# Primary_MCU.net
KiCad netlist of a schematic drawn in Altium Designer
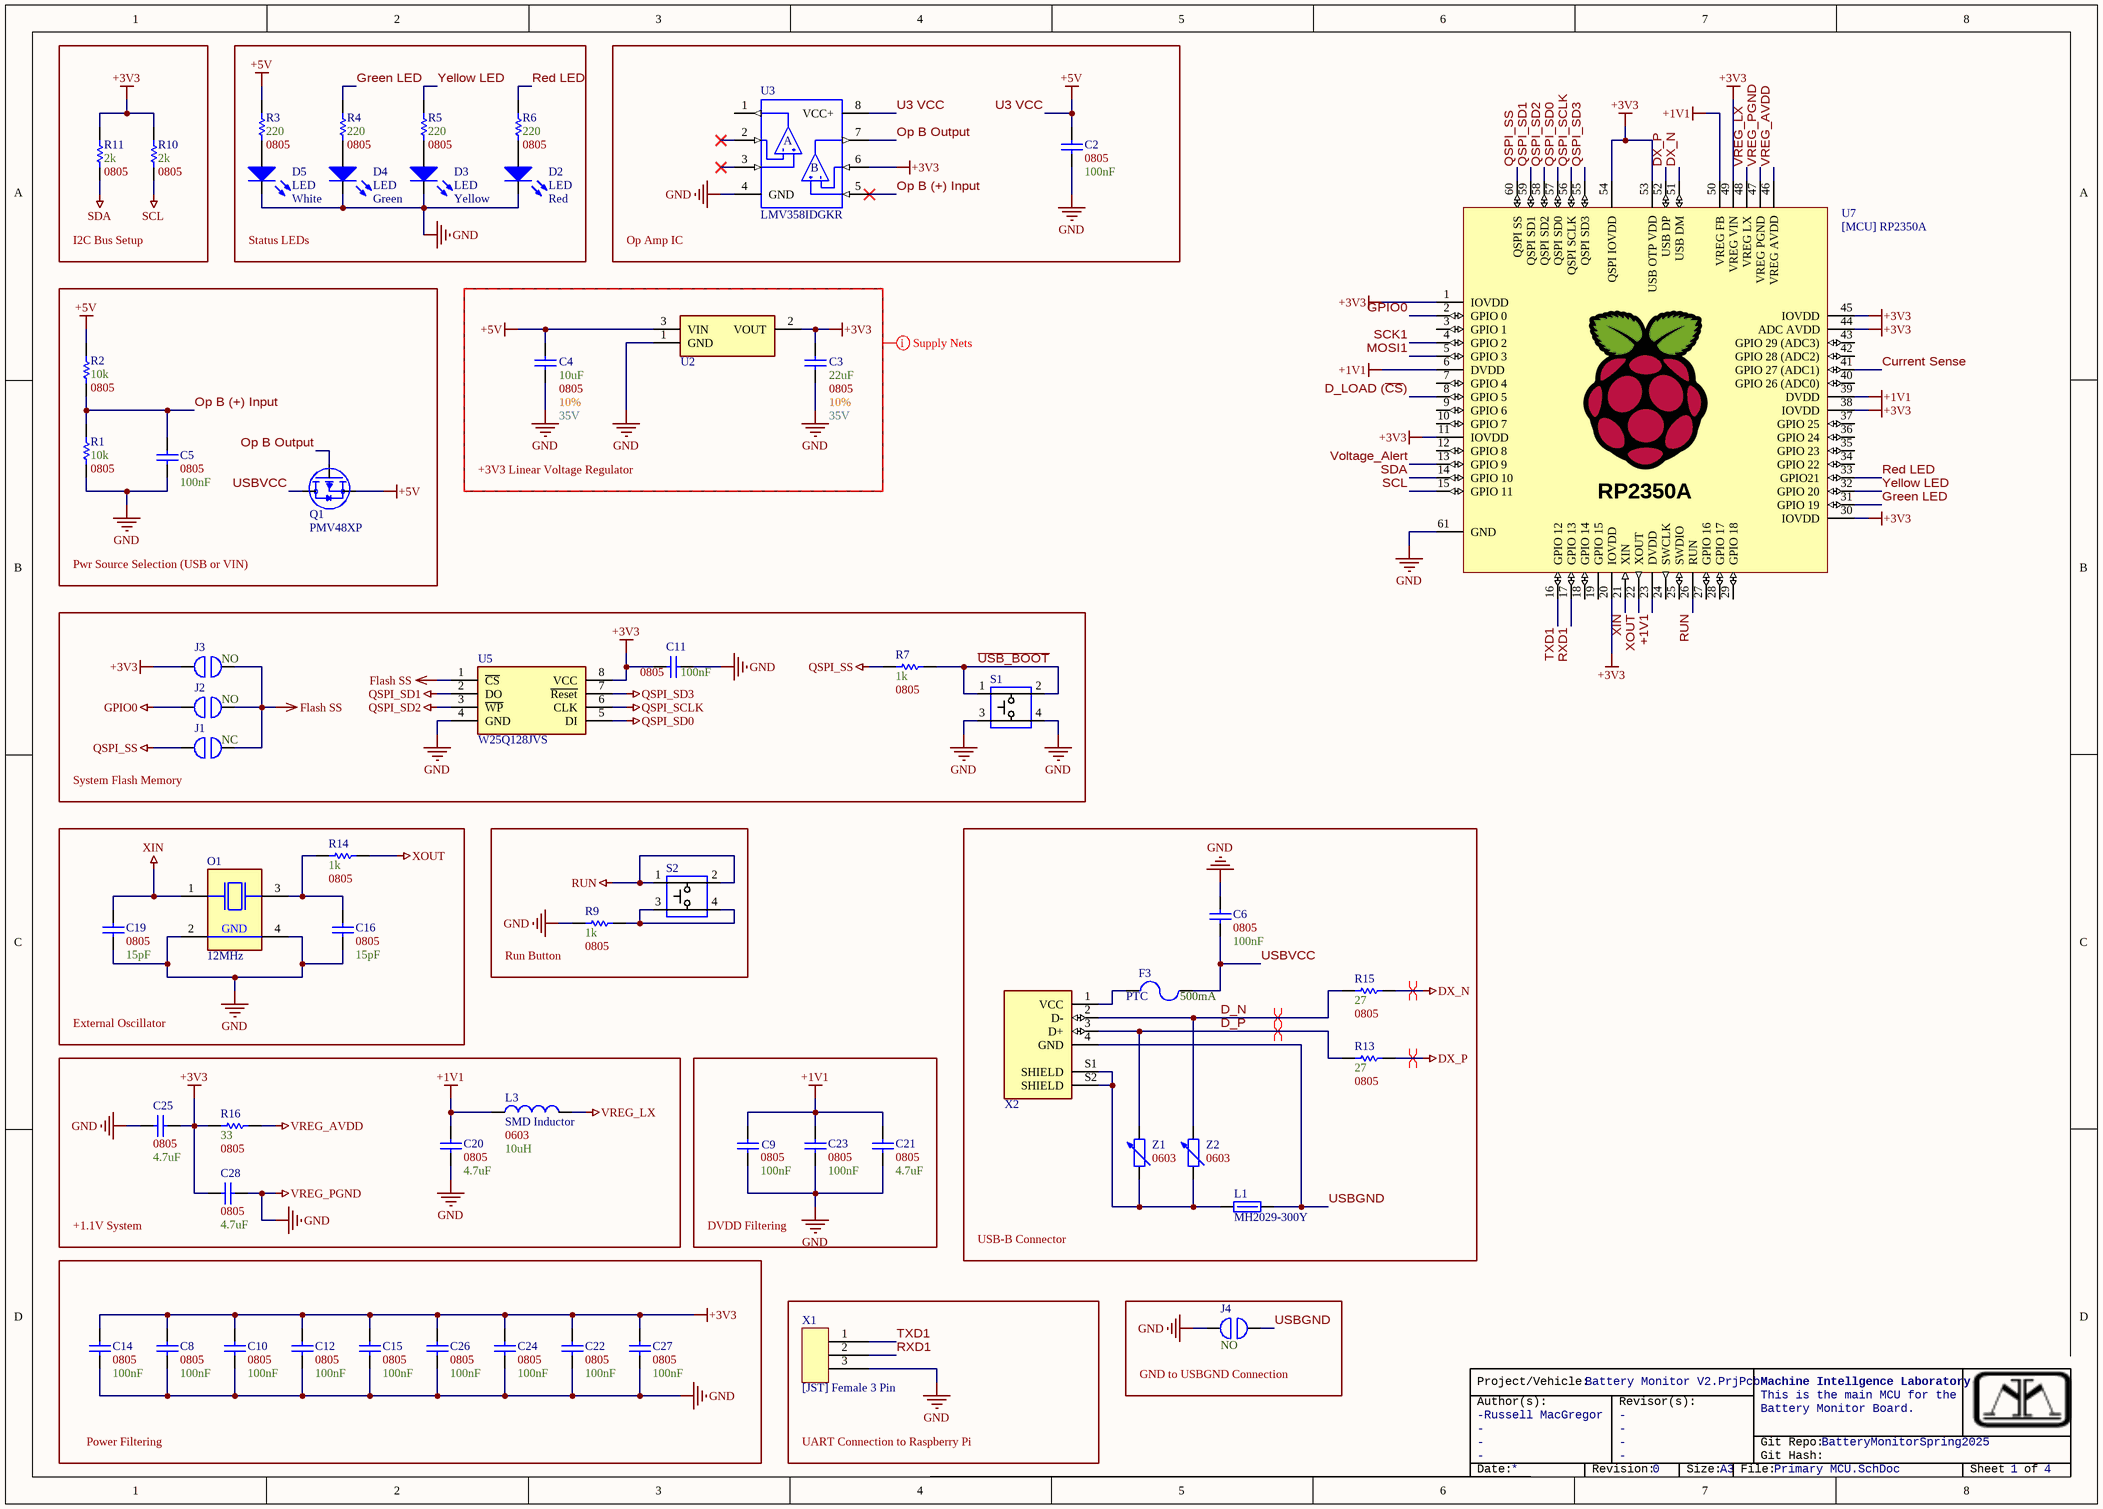
[diagram p0: Primary MCU.SchDoc]

(export (version "E")
  (design (tool "Eeschema 10.0.6"))
  (components
    (comp (ref "C2")
      (value "[Cap] SMD Nonpolarized")
      (footprint "[Cap] SMD 0805")
      (fields (field (name "SIZE PACKAGE") "0805") (field (name "CAPACITANCE") "100nF"))
      (libsource (lib "RADM Components") (part "[Cap] SMD Nonpolarized"))
    )
    (comp (ref "C3")
      (value "SMD Nonpolarized")
      (footprint "[Cap] SMD 0805")
      (fields
        (field (name "VOLTAGE") "35V")
        (field (name "TOLERANCE") "10%")
        (field (name "SIZE PACKAGE") "0805")
        (field (name "CAPACITANCE") "22uF")
      )
      (libsource (lib "RADM Components") (part "[Cap] SMD Nonpolarized"))
    )
    (comp (ref "C4")
      (value "SMD Nonpolarized")
      (footprint "[Cap] SMD 0805")
      (fields
        (field (name "VOLTAGE") "35V")
        (field (name "TOLERANCE") "10%")
        (field (name "SIZE PACKAGE") "0805")
        (field (name "CAPACITANCE") "10uF")
      )
      (libsource (lib "RADM Components") (part "[Cap] SMD Nonpolarized"))
    )
    (comp (ref "C5")
      (value "[Cap] SMD Nonpolarized")
      (footprint "[Cap] SMD 0805")
      (fields (field (name "SIZE PACKAGE") "0805") (field (name "CAPACITANCE") "100nF"))
      (libsource (lib "RADM Components") (part "[Cap] SMD Nonpolarized"))
    )
    (comp (ref "C6")
      (value "[Cap] SMD Nonpolarized")
      (footprint "[Cap] SMD 0805")
      (fields (field (name "SIZE PACKAGE") "0805") (field (name "CAPACITANCE") "100nF"))
      (libsource (lib "RADM Components") (part "[Cap] SMD Nonpolarized"))
    )
    (comp (ref "C8")
      (value "[Cap] SMD Nonpolarized")
      (footprint "[Cap] SMD 0805")
      (fields (field (name "SIZE PACKAGE") "0805") (field (name "CAPACITANCE") "100nF"))
      (libsource (lib "RADM Components") (part "[Cap] SMD Nonpolarized"))
    )
    (comp (ref "C9")
      (value "[Cap] SMD Nonpolarized")
      (footprint "[Cap] SMD 0805")
      (fields (field (name "SIZE PACKAGE") "0805") (field (name "CAPACITANCE") "100nF"))
      (libsource (lib "RADM Components") (part "[Cap] SMD Nonpolarized"))
    )
    (comp (ref "C10")
      (value "[Cap] SMD Nonpolarized")
      (footprint "[Cap] SMD 0805")
      (fields (field (name "SIZE PACKAGE") "0805") (field (name "CAPACITANCE") "100nF"))
      (libsource (lib "RADM Components") (part "[Cap] SMD Nonpolarized"))
    )
    (comp (ref "C11")
      (value "[Cap] SMD Nonpolarized")
      (footprint "[Cap] SMD 0805")
      (fields (field (name "SIZE PACKAGE") "0805") (field (name "CAPACITANCE") "100nF"))
      (libsource (lib "RADM Components") (part "[Cap] SMD Nonpolarized"))
    )
    (comp (ref "C12")
      (value "[Cap] SMD Nonpolarized")
      (footprint "[Cap] SMD 0805")
      (fields (field (name "SIZE PACKAGE") "0805") (field (name "CAPACITANCE") "100nF"))
      (libsource (lib "RADM Components") (part "[Cap] SMD Nonpolarized"))
    )
    (comp (ref "C14")
      (value "[Cap] SMD Nonpolarized")
      (footprint "[Cap] SMD 0805")
      (fields (field (name "SIZE PACKAGE") "0805") (field (name "CAPACITANCE") "100nF"))
      (libsource (lib "RADM Components") (part "[Cap] SMD Nonpolarized"))
    )
    (comp (ref "C15")
      (value "[Cap] SMD Nonpolarized")
      (footprint "[Cap] SMD 0805")
      (fields (field (name "SIZE PACKAGE") "0805") (field (name "CAPACITANCE") "100nF"))
      (libsource (lib "RADM Components") (part "[Cap] SMD Nonpolarized"))
    )
    (comp (ref "C16")
      (value "[Cap] SMD Nonpolarized")
      (footprint "[Cap] SMD 0805")
      (fields (field (name "SIZE PACKAGE") "0805") (field (name "CAPACITANCE") "15pF"))
      (libsource (lib "RADM Components") (part "[Cap] SMD Nonpolarized"))
    )
    (comp (ref "C19")
      (value "[Cap] SMD Nonpolarized")
      (footprint "[Cap] SMD 0805")
      (fields (field (name "SIZE PACKAGE") "0805") (field (name "CAPACITANCE") "15pF"))
      (libsource (lib "RADM Components") (part "[Cap] SMD Nonpolarized"))
    )
    (comp (ref "C20")
      (value "[Cap] SMD Nonpolarized")
      (footprint "[Cap] SMD 0805")
      (fields (field (name "SIZE PACKAGE") "0805") (field (name "CAPACITANCE") "4.7uF"))
      (libsource (lib "RADM Components") (part "[Cap] SMD Nonpolarized"))
    )
    (comp (ref "C21")
      (value "[Cap] SMD Nonpolarized")
      (footprint "[Cap] SMD 0805")
      (fields (field (name "SIZE PACKAGE") "0805") (field (name "CAPACITANCE") "4.7uF"))
      (libsource (lib "RADM Components") (part "[Cap] SMD Nonpolarized"))
    )
    (comp (ref "C22")
      (value "[Cap] SMD Nonpolarized")
      (footprint "[Cap] SMD 0805")
      (fields (field (name "SIZE PACKAGE") "0805") (field (name "CAPACITANCE") "100nF"))
      (libsource (lib "RADM Components") (part "[Cap] SMD Nonpolarized"))
    )
    (comp (ref "C23")
      (value "[Cap] SMD Nonpolarized")
      (footprint "[Cap] SMD 0805")
      (fields (field (name "SIZE PACKAGE") "0805") (field (name "CAPACITANCE") "100nF"))
      (libsource (lib "RADM Components") (part "[Cap] SMD Nonpolarized"))
    )
    (comp (ref "C24")
      (value "[Cap] SMD Nonpolarized")
      (footprint "[Cap] SMD 0805")
      (fields (field (name "SIZE PACKAGE") "0805") (field (name "CAPACITANCE") "100nF"))
      (libsource (lib "RADM Components") (part "[Cap] SMD Nonpolarized"))
    )
    (comp (ref "C25")
      (value "[Cap] SMD Nonpolarized")
      (footprint "[Cap] SMD 0805")
      (fields (field (name "SIZE PACKAGE") "0805") (field (name "CAPACITANCE") "4.7uF"))
      (libsource (lib "RADM Components") (part "[Cap] SMD Nonpolarized"))
    )
    (comp (ref "C26")
      (value "[Cap] SMD Nonpolarized")
      (footprint "[Cap] SMD 0805")
      (fields (field (name "SIZE PACKAGE") "0805") (field (name "CAPACITANCE") "100nF"))
      (libsource (lib "RADM Components") (part "[Cap] SMD Nonpolarized"))
    )
    (comp (ref "C27")
      (value "[Cap] SMD Nonpolarized")
      (footprint "[Cap] SMD 0805")
      (fields (field (name "SIZE PACKAGE") "0805") (field (name "CAPACITANCE") "100nF"))
      (libsource (lib "RADM Components") (part "[Cap] SMD Nonpolarized"))
    )
    (comp (ref "C28")
      (value "[Cap] SMD Nonpolarized")
      (footprint "[Cap] SMD 0805")
      (fields (field (name "SIZE PACKAGE") "0805") (field (name "CAPACITANCE") "4.7uF"))
      (libsource (lib "RADM Components") (part "[Cap] SMD Nonpolarized"))
    )
    (comp (ref "D2")
      (value "LED")
      (footprint "[LED] Thru-Hole, 3mm, Red")
      (description "3mm LED")
      (fields (field (name "COLOR") "Red"))
      (libsource (lib "RADM Components") (part "[LED] Thru-Hole 3mm"))
    )
    (comp (ref "D3")
      (value "LED")
      (footprint "[LED] Thru-Hole, 3mm, Yellow")
      (description "3mm LED")
      (fields (field (name "COLOR") "Yellow"))
      (libsource (lib "RADM Components") (part "[LED] Thru-Hole 3mm"))
    )
    (comp (ref "D4")
      (value "LED")
      (footprint "[LED] Thru-Hole, 3mm, Green")
      (description "3mm LED")
      (fields (field (name "COLOR") "Green"))
      (libsource (lib "RADM Components") (part "[LED] Thru-Hole 3mm"))
    )
    (comp (ref "D5")
      (value "LED")
      (footprint "[LED] Thru-Hole, 3mm, White")
      (description "3mm LED")
      (fields (field (name "COLOR") "White"))
      (libsource (lib "RADM Components") (part "[LED] Thru-Hole 3mm"))
    )
    (comp (ref "F3")
      (value "PTC")
      (footprint "[PTC] 500mA Trip")
      (description "MF-MSMF050-2\r\nJLC Part #: C17313")
      (fields (field (name "JLC PART #") "C17313") (field (name "TRIP CURRENT") "500mA"))
      (libsource (lib "RADM Components") (part "[PTC] 500mA Trip"))
    )
    (comp (ref "J1")
      (value "[Jump] SMD Jumper")
      (footprint "[Jumper] Solderable Jumper")
      (description "Solderable jumper")
      (fields (field (name "NO/NC") "NC"))
      (libsource (lib "RADM Components") (part "[Jump] SMD Jumper"))
    )
    (comp (ref "J2")
      (value "[Jump] SMD Jumper")
      (footprint "[Jumper] Solderable Jumper")
      (description "Solderable jumper")
      (fields (field (name "NO/NC") "NO"))
      (libsource (lib "RADM Components") (part "[Jump] SMD Jumper"))
    )
    (comp (ref "J3")
      (value "[Jump] SMD Jumper")
      (footprint "[Jumper] Solderable Jumper")
      (description "Solderable jumper")
      (fields (field (name "NO/NC") "NO"))
      (libsource (lib "RADM Components") (part "[Jump] SMD Jumper"))
    )
    (comp (ref "J4")
      (value "[Jump] SMD Jumper")
      (footprint "[Jumper] Solderable Jumper")
      (description "Solderable jumper")
      (fields (field (name "NO/NC") "NO"))
      (libsource (lib "RADM Components") (part "[Jump] SMD Jumper"))
    )
    (comp (ref "L1")
      (value "MH2029-300Y")
      (footprint "[Ferrite] SMD Bead 0805 (1)")
      (description "652-MH2029-300Y")
      (libsource (lib "RADM Components") (part "[Ferrite] SMD Ferrite Bead (1)"))
    )
    (comp (ref "L3")
      (value "SMD Inductor")
      (footprint "[Inductor] SMD 0603")
      (fields (field (name "SIZE PACKAGE") "0603") (field (name "INDUCTANCE") "10uH"))
      (libsource (lib "RADM Components") (part "[Inductor] SMD Inductor"))
    )
    (comp (ref "O1")
      (value "12MHz")
      (footprint "[XTAL] SMD 12MHz")
      (description "815-ABM8-272-T3")
      (libsource (lib "RADM Components") (part "[XTAL] SMD 12MHz"))
    )
    (comp (ref "Q1")
      (value "PMV48XP")
      (footprint "[FET] P-Channel Mosfet")
      (fields (field (name "JLC PART #") "C2959854"))
      (libsource (lib "RADM Components") (part "[FET] P-Channel MOSFET"))
    )
    (comp (ref "R1")
      (value "[Res] SMD Resistor")
      (footprint "[Res] SMD 0805")
      (fields (field (name "RESISTANCE") "10k") (field (name "SIZE PACKAGE") "0805"))
      (libsource (lib "RADM Components") (part "[Res] SMD Resistor"))
    )
    (comp (ref "R2")
      (value "[Res] SMD Resistor")
      (footprint "[Res] SMD 0805")
      (fields (field (name "RESISTANCE") "10k") (field (name "SIZE PACKAGE") "0805"))
      (libsource (lib "RADM Components") (part "[Res] SMD Resistor"))
    )
    (comp (ref "R3")
      (value "[Res] SMD Resistor")
      (footprint "[Res] SMD 0805")
      (fields (field (name "RESISTANCE") "220") (field (name "SIZE PACKAGE") "0805"))
      (libsource (lib "RADM Components") (part "[Res] SMD Resistor"))
    )
    (comp (ref "R4")
      (value "[Res] SMD Resistor")
      (footprint "[Res] SMD 0805")
      (fields (field (name "RESISTANCE") "220") (field (name "SIZE PACKAGE") "0805"))
      (libsource (lib "RADM Components") (part "[Res] SMD Resistor"))
    )
    (comp (ref "R5")
      (value "[Res] SMD Resistor")
      (footprint "[Res] SMD 0805")
      (fields (field (name "RESISTANCE") "220") (field (name "SIZE PACKAGE") "0805"))
      (libsource (lib "RADM Components") (part "[Res] SMD Resistor"))
    )
    (comp (ref "R6")
      (value "[Res] SMD Resistor")
      (footprint "[Res] SMD 0805")
      (fields (field (name "RESISTANCE") "220") (field (name "SIZE PACKAGE") "0805"))
      (libsource (lib "RADM Components") (part "[Res] SMD Resistor"))
    )
    (comp (ref "R7")
      (value "[Res] SMD Resistor")
      (footprint "[Res] SMD 0805")
      (fields (field (name "RESISTANCE") "1k") (field (name "SIZE PACKAGE") "0805"))
      (libsource (lib "RADM Components") (part "[Res] SMD Resistor"))
    )
    (comp (ref "R9")
      (value "[Res] SMD Resistor")
      (footprint "[Res] SMD 0805")
      (fields (field (name "RESISTANCE") "1k") (field (name "SIZE PACKAGE") "0805"))
      (libsource (lib "RADM Components") (part "[Res] SMD Resistor"))
    )
    (comp (ref "R10")
      (value "[Res] SMD Resistor")
      (footprint "[Res] SMD 0805")
      (fields (field (name "RESISTANCE") "2k") (field (name "SIZE PACKAGE") "0805"))
      (libsource (lib "RADM Components") (part "[Res] SMD Resistor"))
    )
    (comp (ref "R11")
      (value "[Res] SMD Resistor")
      (footprint "[Res] SMD 0805")
      (fields (field (name "RESISTANCE") "2k") (field (name "SIZE PACKAGE") "0805"))
      (libsource (lib "RADM Components") (part "[Res] SMD Resistor"))
    )
    (comp (ref "R13")
      (value "[Res] SMD Resistor")
      (footprint "[Res] SMD 0805")
      (fields (field (name "RESISTANCE") "27") (field (name "SIZE PACKAGE") "0805"))
      (libsource (lib "RADM Components") (part "[Res] SMD Resistor"))
    )
    (comp (ref "R14")
      (value "[Res] SMD Resistor")
      (footprint "[Res] SMD 0805")
      (fields (field (name "RESISTANCE") "1k") (field (name "SIZE PACKAGE") "0805"))
      (libsource (lib "RADM Components") (part "[Res] SMD Resistor"))
    )
    (comp (ref "R15")
      (value "[Res] SMD Resistor")
      (footprint "[Res] SMD 0805")
      (fields (field (name "RESISTANCE") "27") (field (name "SIZE PACKAGE") "0805"))
      (libsource (lib "RADM Components") (part "[Res] SMD Resistor"))
    )
    (comp (ref "R16")
      (value "[Res] SMD Resistor")
      (footprint "[Res] SMD 0805")
      (fields (field (name "RESISTANCE") "33") (field (name "SIZE PACKAGE") "0805"))
      (libsource (lib "RADM Components") (part "[Res] SMD Resistor"))
    )
    (comp (ref "S1")
      (value "Standard pushbutton")
      (footprint "[Switch] Pushbutton")
      (libsource (lib "RADM Components") (part "[Switch] Pushbutton"))
    )
    (comp (ref "S2")
      (value "Standard pushbutton")
      (footprint "[Switch] Pushbutton")
      (libsource (lib "RADM Components") (part "[Switch] Pushbutton"))
    )
    (comp (ref "U2")
      (value "3V3 1A")
      (footprint "[Reg] 3V3 Regulator (2)")
      (description "AZ1117CH-3.3TRG1")
      (libsource (lib "RADM Components") (part "[Reg] 3V3 Regulator (2)"))
    )
    (comp (ref "U3")
      (value "LMV358IDGKR")
      (footprint "[IC] Dual Op-Ap")
      (fields (field (name "JLC PART #") "C105242"))
      (libsource (lib "RADM Components") (part "[IC] Dual Op-Amp"))
    )
    (comp (ref "U5")
      (value "W25Q128JVS")
      (footprint "[IC] 16Mb Flash Memory")
      (description "W25Q128JVSIQ TR")
      (libsource (lib "RADM Components") (part "[IC] 16Mb Flash Memory"))
    )
    (comp (ref "U7")
      (value "[MCU] RP2350A")
      (footprint "[MCU] RP2350A")
      (libsource (lib "RADM Components") (part "[MCU] RP2350A"))
    )
    (comp (ref "X1")
      (value "[JST] Female 3 Pin")
      (footprint "[JST] 3PIN")
      (libsource (lib "RADM Components") (part "[JST] Female 3 Pin"))
    )
    (comp (ref "X2")
      (value "[Port] USB Type-B Female (Thru-Hole)")
      (footprint "[Port] USB Type-B Thru-Hole")
      (description "USB-B-S-F-B-TH")
      (fields (field (name "JLC PART #") "C5714571"))
      (libsource (lib "RADM Components") (part "[Port] USB Type-B Female (Thru-Hole)"))
    )
    (comp (ref "Z1")
      (value "[Inductor] SMD Varistor")
      (footprint "[Inductor] SMD Varistor 0603")
      (fields (field (name "JLC PART #") "C840634") (field (name "SIZE PACKAGE") "0603"))
      (libsource (lib "RADM Components") (part "[Inductor] SMD Varistor"))
    )
    (comp (ref "Z2")
      (value "[Inductor] SMD Varistor")
      (footprint "[Inductor] SMD Varistor 0603")
      (fields (field (name "JLC PART #") "C840634") (field (name "SIZE PACKAGE") "0603"))
      (libsource (lib "RADM Components") (part "[Inductor] SMD Varistor"))
    )
  )
  (nets
    (net (code "1") (name "+1V1") (class "Default")
      (node (ref "C20") (pin "2") (pinfunction "2_2") (pintype "passive"))
      (node (ref "C21") (pin "2") (pinfunction "2_2") (pintype "passive"))
      (node (ref "C23") (pin "2") (pinfunction "2_2") (pintype "passive"))
      (node (ref "C9") (pin "2") (pinfunction "2_2") (pintype "passive"))
      (node (ref "L3") (pin "1") (pinfunction "1_1") (pintype "passive"))
      (node (ref "U7") (pin "23") (pinfunction "DVDD_23") (pintype "power_in"))
      (node (ref "U7") (pin "39") (pinfunction "DVDD_39") (pintype "power_in"))
      (node (ref "U7") (pin "50") (pinfunction "VREG_FB_50") (pintype "power_in"))
      (node (ref "U7") (pin "6") (pinfunction "DVDD_6") (pintype "power_in"))
    )
    (net (code "2") (name "+3V3") (class "Default")
      (node (ref "C10") (pin "2") (pinfunction "2_2") (pintype "passive"))
      (node (ref "C11") (pin "2") (pinfunction "2_2") (pintype "passive"))
      (node (ref "C12") (pin "2") (pinfunction "2_2") (pintype "passive"))
      (node (ref "C14") (pin "2") (pinfunction "2_2") (pintype "passive"))
      (node (ref "C15") (pin "2") (pinfunction "2_2") (pintype "passive"))
      (node (ref "C22") (pin "2") (pinfunction "2_2") (pintype "passive"))
      (node (ref "C24") (pin "2") (pinfunction "2_2") (pintype "passive"))
      (node (ref "C25") (pin "1") (pinfunction "1_1") (pintype "passive"))
      (node (ref "C26") (pin "2") (pinfunction "2_2") (pintype "passive"))
      (node (ref "C27") (pin "2") (pinfunction "2_2") (pintype "passive"))
      (node (ref "C28") (pin "2") (pinfunction "2_2") (pintype "passive"))
      (node (ref "C3") (pin "2") (pinfunction "2_2") (pintype "passive"))
      (node (ref "C8") (pin "2") (pinfunction "2_2") (pintype "passive"))
      (node (ref "J3") (pin "1") (pintype "passive"))
      (node (ref "R10") (pin "2") (pinfunction "2_2") (pintype "passive"))
      (node (ref "R11") (pin "2") (pinfunction "2_2") (pintype "passive"))
      (node (ref "R16") (pin "2") (pinfunction "2_2") (pintype "passive"))
      (node (ref "U2") (pin "2") (pinfunction "VOUT_2") (pintype "passive"))
      (node (ref "U3") (pin "6") (pinfunction "2IN-_6") (pintype "input"))
      (node (ref "U5") (pin "8") (pinfunction "VCC_8") (pintype "passive"))
      (node (ref "U7") (pin "1") (pinfunction "IOVDD_1") (pintype "power_in"))
      (node (ref "U7") (pin "11") (pinfunction "IOVDD_11") (pintype "power_in"))
      (node (ref "U7") (pin "20") (pinfunction "IOVDD_20") (pintype "power_in"))
      (node (ref "U7") (pin "30") (pinfunction "IOVDD_30") (pintype "power_in"))
      (node (ref "U7") (pin "38") (pinfunction "IOVDD_38") (pintype "power_in"))
      (node (ref "U7") (pin "44") (pinfunction "ADC_AVDD_44") (pintype "power_in"))
      (node (ref "U7") (pin "45") (pinfunction "IOVDD_45") (pintype "power_in"))
      (node (ref "U7") (pin "49") (pinfunction "VREG_VIN_49") (pintype "power_in"))
      (node (ref "U7") (pin "53") (pinfunction "USB_OTP_VDD_53") (pintype "power_in"))
      (node (ref "U7") (pin "54") (pinfunction "QSPI_IOVDD_54") (pintype "power_in"))
    )
    (net (code "3") (name "+5V") (class "Default")
      (node (ref "C2") (pin "2") (pinfunction "2_2") (pintype "passive"))
      (node (ref "C4") (pin "2") (pinfunction "2_2") (pintype "passive"))
      (node (ref "Q1") (pin "2") (pinfunction "S_2") (pintype "passive"))
      (node (ref "R2") (pin "2") (pinfunction "2_2") (pintype "passive"))
      (node (ref "R3") (pin "1") (pinfunction "1_1") (pintype "passive"))
      (node (ref "U2") (pin "3") (pinfunction "VIN_3") (pintype "passive"))
      (node (ref "U3") (pin "8") (pinfunction "VCC+_8") (pintype "power_in"))
    )
    (net (code "4") (name "/Current Sense") (class "Default")
      (node (ref "U7") (pin "41") (pinfunction "GPIO_27_(ADC1)_41") (pintype "bidirectional"))
    )
    (net (code "5") (name "/D_LOAD (~{CS})") (class "Default")
      (node (ref "U7") (pin "8") (pinfunction "GPIO_5_8") (pintype "bidirectional"))
    )
    (net (code "6") (name "/D_N") (class "Default")
      (node (ref "R15") (pin "2") (pinfunction "2_2") (pintype "passive"))
      (node (ref "X2") (pin "2") (pinfunction "D-_2") (pintype "bidirectional"))
      (node (ref "Z2") (pin "2") (pinfunction "2_2") (pintype "passive"))
    )
    (net (code "7") (name "/D_P") (class "Default")
      (node (ref "R13") (pin "2") (pinfunction "2_2") (pintype "passive"))
      (node (ref "X2") (pin "3") (pinfunction "D+_3") (pintype "bidirectional"))
      (node (ref "Z1") (pin "2") (pinfunction "2_2") (pintype "passive"))
    )
    (net (code "8") (name "/Green LED") (class "Default")
      (node (ref "R4") (pin "1") (pinfunction "1_1") (pintype "passive"))
      (node (ref "U7") (pin "31") (pinfunction "GPIO_19_31") (pintype "bidirectional"))
    )
    (net (code "9") (name "/MOSI1") (class "Default")
      (node (ref "U7") (pin "5") (pinfunction "GPIO_3_5") (pintype "bidirectional"))
    )
    (net (code "10") (name "/Op B (+) Input") (class "Default")
      (node (ref "C5") (pin "2") (pinfunction "2_2") (pintype "passive"))
      (node (ref "R1") (pin "2") (pinfunction "2_2") (pintype "passive"))
      (node (ref "R2") (pin "1") (pinfunction "1_1") (pintype "passive"))
      (node (ref "U3") (pin "5") (pinfunction "2IN+_5") (pintype "input"))
    )
    (net (code "11") (name "/Op B Output") (class "Default")
      (node (ref "Q1") (pin "1") (pinfunction "G_1") (pintype "passive"))
      (node (ref "U3") (pin "7") (pinfunction "2OUT_7") (pintype "output"))
    )
    (net (code "12") (name "/RXD1") (class "Default")
      (node (ref "U7") (pin "17") (pinfunction "GPIO_13_17") (pintype "bidirectional"))
      (node (ref "X1") (pin "2") (pintype "passive"))
    )
    (net (code "13") (name "/Red LED") (class "Default")
      (node (ref "R6") (pin "1") (pinfunction "1_1") (pintype "passive"))
      (node (ref "U7") (pin "33") (pinfunction "GPIO21_33") (pintype "bidirectional"))
    )
    (net (code "14") (name "/SCK1") (class "Default")
      (node (ref "U7") (pin "4") (pinfunction "GPIO_2_4") (pintype "bidirectional"))
    )
    (net (code "15") (name "/TXD1") (class "Default")
      (node (ref "U7") (pin "16") (pinfunction "GPIO_12_16") (pintype "bidirectional"))
      (node (ref "X1") (pin "1") (pintype "passive"))
    )
    (net (code "16") (name "/USBGND") (class "Default")
      (node (ref "J4") (pin "2") (pintype "passive"))
      (node (ref "L1") (pin "2") (pinfunction "2_2") (pintype "passive"))
      (node (ref "X2") (pin "4") (pinfunction "GND_4") (pintype "power_in"))
    )
    (net (code "17") (name "/USBVCC") (class "Default")
      (node (ref "C6") (pin "1") (pinfunction "1_1") (pintype "passive"))
      (node (ref "F3") (pin "2") (pinfunction "2_2") (pintype "passive"))
      (node (ref "Q1") (pin "3") (pinfunction "D_3") (pintype "passive"))
    )
    (net (code "18") (name "/Voltage_Alert") (class "Default")
      (node (ref "U7") (pin "13") (pinfunction "GPIO_9_13") (pintype "bidirectional"))
    )
    (net (code "19") (name "/Yellow LED") (class "Default")
      (node (ref "R5") (pin "1") (pinfunction "1_1") (pintype "passive"))
      (node (ref "U7") (pin "32") (pinfunction "GPIO_20_32") (pintype "bidirectional"))
    )
    (net (code "20") (name "/~{USB_BOOT}") (class "Default")
      (node (ref "R7") (pin "1") (pinfunction "1_1") (pintype "passive"))
      (node (ref "S1") (pin "1") (pintype "power_in"))
      (node (ref "S1") (pin "2") (pintype "power_in"))
    )
    (net (code "21") (name "DX_N") (class "Default")
      (node (ref "R15") (pin "1") (pinfunction "1_1") (pintype "passive"))
      (node (ref "U7") (pin "51") (pinfunction "USB_DM_51") (pintype "bidirectional"))
    )
    (net (code "22") (name "DX_P") (class "Default")
      (node (ref "R13") (pin "1") (pinfunction "1_1") (pintype "passive"))
      (node (ref "U7") (pin "52") (pinfunction "USB_DP_52") (pintype "bidirectional"))
    )
    (net (code "23") (name "Flash SS") (class "Default")
      (node (ref "J1") (pin "2") (pintype "passive"))
      (node (ref "J2") (pin "2") (pintype "passive"))
      (node (ref "J3") (pin "2") (pintype "passive"))
      (node (ref "U5") (pin "1") (pinfunction "~{CS}_1") (pintype "passive"))
    )
    (net (code "24") (name "GND") (class "Default")
      (node (ref "C10") (pin "1") (pinfunction "1_1") (pintype "passive"))
      (node (ref "C11") (pin "1") (pinfunction "1_1") (pintype "passive"))
      (node (ref "C12") (pin "1") (pinfunction "1_1") (pintype "passive"))
      (node (ref "C14") (pin "1") (pinfunction "1_1") (pintype "passive"))
      (node (ref "C15") (pin "1") (pinfunction "1_1") (pintype "passive"))
      (node (ref "C16") (pin "1") (pinfunction "1_1") (pintype "passive"))
      (node (ref "C19") (pin "1") (pinfunction "1_1") (pintype "passive"))
      (node (ref "C2") (pin "1") (pinfunction "1_1") (pintype "passive"))
      (node (ref "C20") (pin "1") (pinfunction "1_1") (pintype "passive"))
      (node (ref "C21") (pin "1") (pinfunction "1_1") (pintype "passive"))
      (node (ref "C22") (pin "1") (pinfunction "1_1") (pintype "passive"))
      (node (ref "C23") (pin "1") (pinfunction "1_1") (pintype "passive"))
      (node (ref "C24") (pin "1") (pinfunction "1_1") (pintype "passive"))
      (node (ref "C25") (pin "2") (pinfunction "2_2") (pintype "passive"))
      (node (ref "C26") (pin "1") (pinfunction "1_1") (pintype "passive"))
      (node (ref "C27") (pin "1") (pinfunction "1_1") (pintype "passive"))
      (node (ref "C28") (pin "1") (pinfunction "1_1") (pintype "passive"))
      (node (ref "C3") (pin "1") (pinfunction "1_1") (pintype "passive"))
      (node (ref "C4") (pin "1") (pinfunction "1_1") (pintype "passive"))
      (node (ref "C5") (pin "1") (pinfunction "1_1") (pintype "passive"))
      (node (ref "C6") (pin "2") (pinfunction "2_2") (pintype "passive"))
      (node (ref "C8") (pin "1") (pinfunction "1_1") (pintype "passive"))
      (node (ref "C9") (pin "1") (pinfunction "1_1") (pintype "passive"))
      (node (ref "D2") (pin "2") (pinfunction "K_2") (pintype "passive"))
      (node (ref "D3") (pin "2") (pinfunction "K_2") (pintype "passive"))
      (node (ref "D4") (pin "2") (pinfunction "K_2") (pintype "passive"))
      (node (ref "D5") (pin "2") (pinfunction "K_2") (pintype "passive"))
      (node (ref "J4") (pin "1") (pintype "passive"))
      (node (ref "O1") (pin "2") (pinfunction "GND_2") (pintype "power_in"))
      (node (ref "O1") (pin "4") (pinfunction "GND_4") (pintype "power_in"))
      (node (ref "R1") (pin "1") (pinfunction "1_1") (pintype "passive"))
      (node (ref "R9") (pin "2") (pinfunction "2_2") (pintype "passive"))
      (node (ref "S1") (pin "3") (pintype "power_in"))
      (node (ref "S1") (pin "4") (pintype "power_in"))
      (node (ref "U2") (pin "1") (pinfunction "GND_1") (pintype "passive"))
      (node (ref "U3") (pin "4") (pinfunction "GND_4") (pintype "power_in"))
      (node (ref "U5") (pin "4") (pinfunction "GND_4") (pintype "passive"))
      (node (ref "U7") (pin "47") (pinfunction "VREG_PGND_47") (pintype "power_in"))
      (node (ref "U7") (pin "61") (pinfunction "GND_61") (pintype "power_in"))
      (node (ref "X1") (pin "3") (pintype "passive"))
    )
    (net (code "25") (name "GPIO0") (class "Default")
      (node (ref "J2") (pin "1") (pintype "passive"))
      (node (ref "U7") (pin "2") (pinfunction "GPIO_0_2") (pintype "bidirectional"))
    )
    (net (code "26") (name "Net-(D2-A)") (class "Default")
      (node (ref "D2") (pin "1") (pinfunction "A_1") (pintype "passive"))
      (node (ref "R6") (pin "2") (pinfunction "2_2") (pintype "passive"))
    )
    (net (code "27") (name "Net-(D3-A)") (class "Default")
      (node (ref "D3") (pin "1") (pinfunction "A_1") (pintype "passive"))
      (node (ref "R5") (pin "2") (pinfunction "2_2") (pintype "passive"))
    )
    (net (code "28") (name "Net-(D4-A)") (class "Default")
      (node (ref "D4") (pin "1") (pinfunction "A_1") (pintype "passive"))
      (node (ref "R4") (pin "2") (pinfunction "2_2") (pintype "passive"))
    )
    (net (code "29") (name "Net-(D5-A)") (class "Default")
      (node (ref "D5") (pin "1") (pinfunction "A_1") (pintype "passive"))
      (node (ref "R3") (pin "2") (pinfunction "2_2") (pintype "passive"))
    )
    (net (code "30") (name "Net-(L1-Pad1)") (class "Default")
      (node (ref "L1") (pin "1") (pinfunction "1_1") (pintype "passive"))
      (node (ref "X2") (pin "S1") (pinfunction "SHIELD_S1") (pintype "passive"))
      (node (ref "X2") (pin "S2") (pinfunction "SHIELD_S2") (pintype "passive"))
      (node (ref "Z1") (pin "1") (pinfunction "1_1") (pintype "passive"))
      (node (ref "Z2") (pin "1") (pinfunction "1_1") (pintype "passive"))
    )
    (net (code "31") (name "Net-(O1-XTAL2)") (class "Default")
      (node (ref "C16") (pin "2") (pinfunction "2_2") (pintype "passive"))
      (node (ref "O1") (pin "3") (pinfunction "XTAL2_3") (pintype "power_in"))
      (node (ref "R14") (pin "2") (pinfunction "2_2") (pintype "passive"))
    )
    (net (code "32") (name "Net-(R9-Pad1)") (class "Default")
      (node (ref "R9") (pin "1") (pinfunction "1_1") (pintype "passive"))
      (node (ref "S2") (pin "3") (pintype "power_in"))
      (node (ref "S2") (pin "4") (pintype "power_in"))
    )
    (net (code "33") (name "Net-(X2-VCC)") (class "Default")
      (node (ref "F3") (pin "1") (pinfunction "1_1") (pintype "passive"))
      (node (ref "X2") (pin "1") (pinfunction "VCC_1") (pintype "power_in"))
    )
    (net (code "34") (name "QSPI_SCLK") (class "Default")
      (node (ref "U5") (pin "6") (pinfunction "CLK_6") (pintype "passive"))
      (node (ref "U7") (pin "56") (pinfunction "QSPI_SCLK_56") (pintype "bidirectional"))
    )
    (net (code "35") (name "QSPI_SD0") (class "Default")
      (node (ref "U5") (pin "5") (pinfunction "DI_5") (pintype "passive"))
      (node (ref "U7") (pin "57") (pinfunction "QSPI_SD0_57") (pintype "bidirectional"))
    )
    (net (code "36") (name "QSPI_SD1") (class "Default")
      (node (ref "U5") (pin "2") (pinfunction "DO_2") (pintype "passive"))
      (node (ref "U7") (pin "59") (pinfunction "QSPI_SD1_59") (pintype "bidirectional"))
    )
    (net (code "37") (name "QSPI_SD2") (class "Default")
      (node (ref "U5") (pin "3") (pinfunction "~{WP}_3") (pintype "passive"))
      (node (ref "U7") (pin "58") (pinfunction "QSPI_SD2_58") (pintype "bidirectional"))
    )
    (net (code "38") (name "QSPI_SD3") (class "Default")
      (node (ref "U5") (pin "7") (pinfunction "~{Reset}_7") (pintype "passive"))
      (node (ref "U7") (pin "55") (pinfunction "QSPI_SD3_55") (pintype "bidirectional"))
    )
    (net (code "39") (name "QSPI_SS") (class "Default")
      (node (ref "J1") (pin "1") (pintype "passive"))
      (node (ref "R7") (pin "2") (pinfunction "2_2") (pintype "passive"))
      (node (ref "U7") (pin "60") (pinfunction "QSPI_SS_60") (pintype "bidirectional"))
    )
    (net (code "40") (name "RUN") (class "Default")
      (node (ref "S2") (pin "1") (pintype "power_in"))
      (node (ref "S2") (pin "2") (pintype "power_in"))
      (node (ref "U7") (pin "26") (pinfunction "RUN_26") (pintype "passive"))
    )
    (net (code "41") (name "SCL") (class "Default")
      (node (ref "R10") (pin "1") (pinfunction "1_1") (pintype "passive"))
      (node (ref "U7") (pin "15") (pinfunction "GPIO_11_15") (pintype "bidirectional"))
    )
    (net (code "42") (name "SDA") (class "Default")
      (node (ref "R11") (pin "1") (pinfunction "1_1") (pintype "passive"))
      (node (ref "U7") (pin "14") (pinfunction "GPIO_10_14") (pintype "bidirectional"))
    )
    (net (code "43") (name "VREG_AVDD") (class "Default")
      (node (ref "R16") (pin "1") (pinfunction "1_1") (pintype "passive"))
      (node (ref "U7") (pin "46") (pinfunction "VREG_AVDD_46") (pintype "power_in"))
    )
    (net (code "44") (name "VREG_LX") (class "Default")
      (node (ref "L3") (pin "2") (pinfunction "2_2") (pintype "passive"))
      (node (ref "U7") (pin "48") (pinfunction "VREG_LX_48") (pintype "power_in"))
    )
    (net (code "45") (name "XIN") (class "Default")
      (node (ref "C19") (pin "2") (pinfunction "2_2") (pintype "passive"))
      (node (ref "O1") (pin "1") (pinfunction "XTAL1_1") (pintype "power_in"))
      (node (ref "U7") (pin "21") (pinfunction "XIN_21") (pintype "input"))
    )
    (net (code "46") (name "XOUT") (class "Default")
      (node (ref "R14") (pin "1") (pinfunction "1_1") (pintype "passive"))
      (node (ref "U7") (pin "22") (pinfunction "XOUT_22") (pintype "output"))
    )
    (net (code "47") (name "unconnected-(U3-1IN+-Pad3)") (class "Default")
      (node (ref "U3") (pin "3") (pinfunction "1IN+_3") (pintype "input+no_connect"))
    )
    (net (code "48") (name "unconnected-(U3-1IN--Pad2)") (class "Default")
      (node (ref "U3") (pin "2") (pinfunction "1IN-_2") (pintype "input+no_connect"))
    )
    (net (code "49") (name "unconnected-(U3-1OUT-Pad1)") (class "Default")
      (node (ref "U3") (pin "1") (pinfunction "1OUT_1") (pintype "output"))
    )
    (net (code "50") (name "unconnected-(U7-GPIO_1-Pad3)") (class "Default")
      (node (ref "U7") (pin "3") (pinfunction "GPIO_1_3") (pintype "bidirectional"))
    )
    (net (code "51") (name "unconnected-(U7-GPIO_4-Pad7)") (class "Default")
      (node (ref "U7") (pin "7") (pinfunction "GPIO_4_7") (pintype "bidirectional"))
    )
    (net (code "52") (name "unconnected-(U7-GPIO_6-Pad9)") (class "Default")
      (node (ref "U7") (pin "9") (pinfunction "GPIO_6_9") (pintype "bidirectional"))
    )
    (net (code "53") (name "unconnected-(U7-GPIO_7-Pad10)") (class "Default")
      (node (ref "U7") (pin "10") (pinfunction "GPIO_7_10") (pintype "bidirectional"))
    )
    (net (code "54") (name "unconnected-(U7-GPIO_8-Pad12)") (class "Default")
      (node (ref "U7") (pin "12") (pinfunction "GPIO_8_12") (pintype "bidirectional"))
    )
    (net (code "55") (name "unconnected-(U7-GPIO_14-Pad18)") (class "Default")
      (node (ref "U7") (pin "18") (pinfunction "GPIO_14_18") (pintype "bidirectional"))
    )
    (net (code "56") (name "unconnected-(U7-GPIO_15-Pad19)") (class "Default")
      (node (ref "U7") (pin "19") (pinfunction "GPIO_15_19") (pintype "power_in"))
    )
    (net (code "57") (name "unconnected-(U7-GPIO_16-Pad27)") (class "Default")
      (node (ref "U7") (pin "27") (pinfunction "GPIO_16_27") (pintype "bidirectional"))
    )
    (net (code "58") (name "unconnected-(U7-GPIO_17-Pad28)") (class "Default")
      (node (ref "U7") (pin "28") (pinfunction "GPIO_17_28") (pintype "bidirectional"))
    )
    (net (code "59") (name "unconnected-(U7-GPIO_18-Pad29)") (class "Default")
      (node (ref "U7") (pin "29") (pinfunction "GPIO_18_29") (pintype "bidirectional"))
    )
    (net (code "60") (name "unconnected-(U7-GPIO_22-Pad34)") (class "Default")
      (node (ref "U7") (pin "34") (pinfunction "GPIO_22_34") (pintype "bidirectional"))
    )
    (net (code "61") (name "unconnected-(U7-GPIO_23-Pad35)") (class "Default")
      (node (ref "U7") (pin "35") (pinfunction "GPIO_23_35") (pintype "bidirectional"))
    )
    (net (code "62") (name "unconnected-(U7-GPIO_24-Pad36)") (class "Default")
      (node (ref "U7") (pin "36") (pinfunction "GPIO_24_36") (pintype "bidirectional"))
    )
    (net (code "63") (name "unconnected-(U7-GPIO_25-Pad37)") (class "Default")
      (node (ref "U7") (pin "37") (pinfunction "GPIO_25_37") (pintype "bidirectional"))
    )
    (net (code "64") (name "unconnected-(U7-GPIO_26_(ADC0)-Pad40)") (class "Default")
      (node (ref "U7") (pin "40") (pinfunction "GPIO_26_(ADC0)_40") (pintype "bidirectional"))
    )
    (net (code "65") (name "unconnected-(U7-GPIO_28_(ADC2)-Pad42)") (class "Default")
      (node (ref "U7") (pin "42") (pinfunction "GPIO_28_(ADC2)_42") (pintype "bidirectional"))
    )
    (net (code "66") (name "unconnected-(U7-GPIO_29_(ADC3)-Pad43)") (class "Default")
      (node (ref "U7") (pin "43") (pinfunction "GPIO_29_(ADC3)_43") (pintype "bidirectional"))
    )
    (net (code "67") (name "unconnected-(U7-SWCLK-Pad24)") (class "Default")
      (node (ref "U7") (pin "24") (pinfunction "SWCLK_24") (pintype "output"))
    )
    (net (code "68") (name "unconnected-(U7-SWDIO-Pad25)") (class "Default")
      (node (ref "U7") (pin "25") (pinfunction "SWDIO_25") (pintype "bidirectional"))
    )
  )
)
